# ADC.net
KiCad netlist of a schematic drawn in Altium Designer
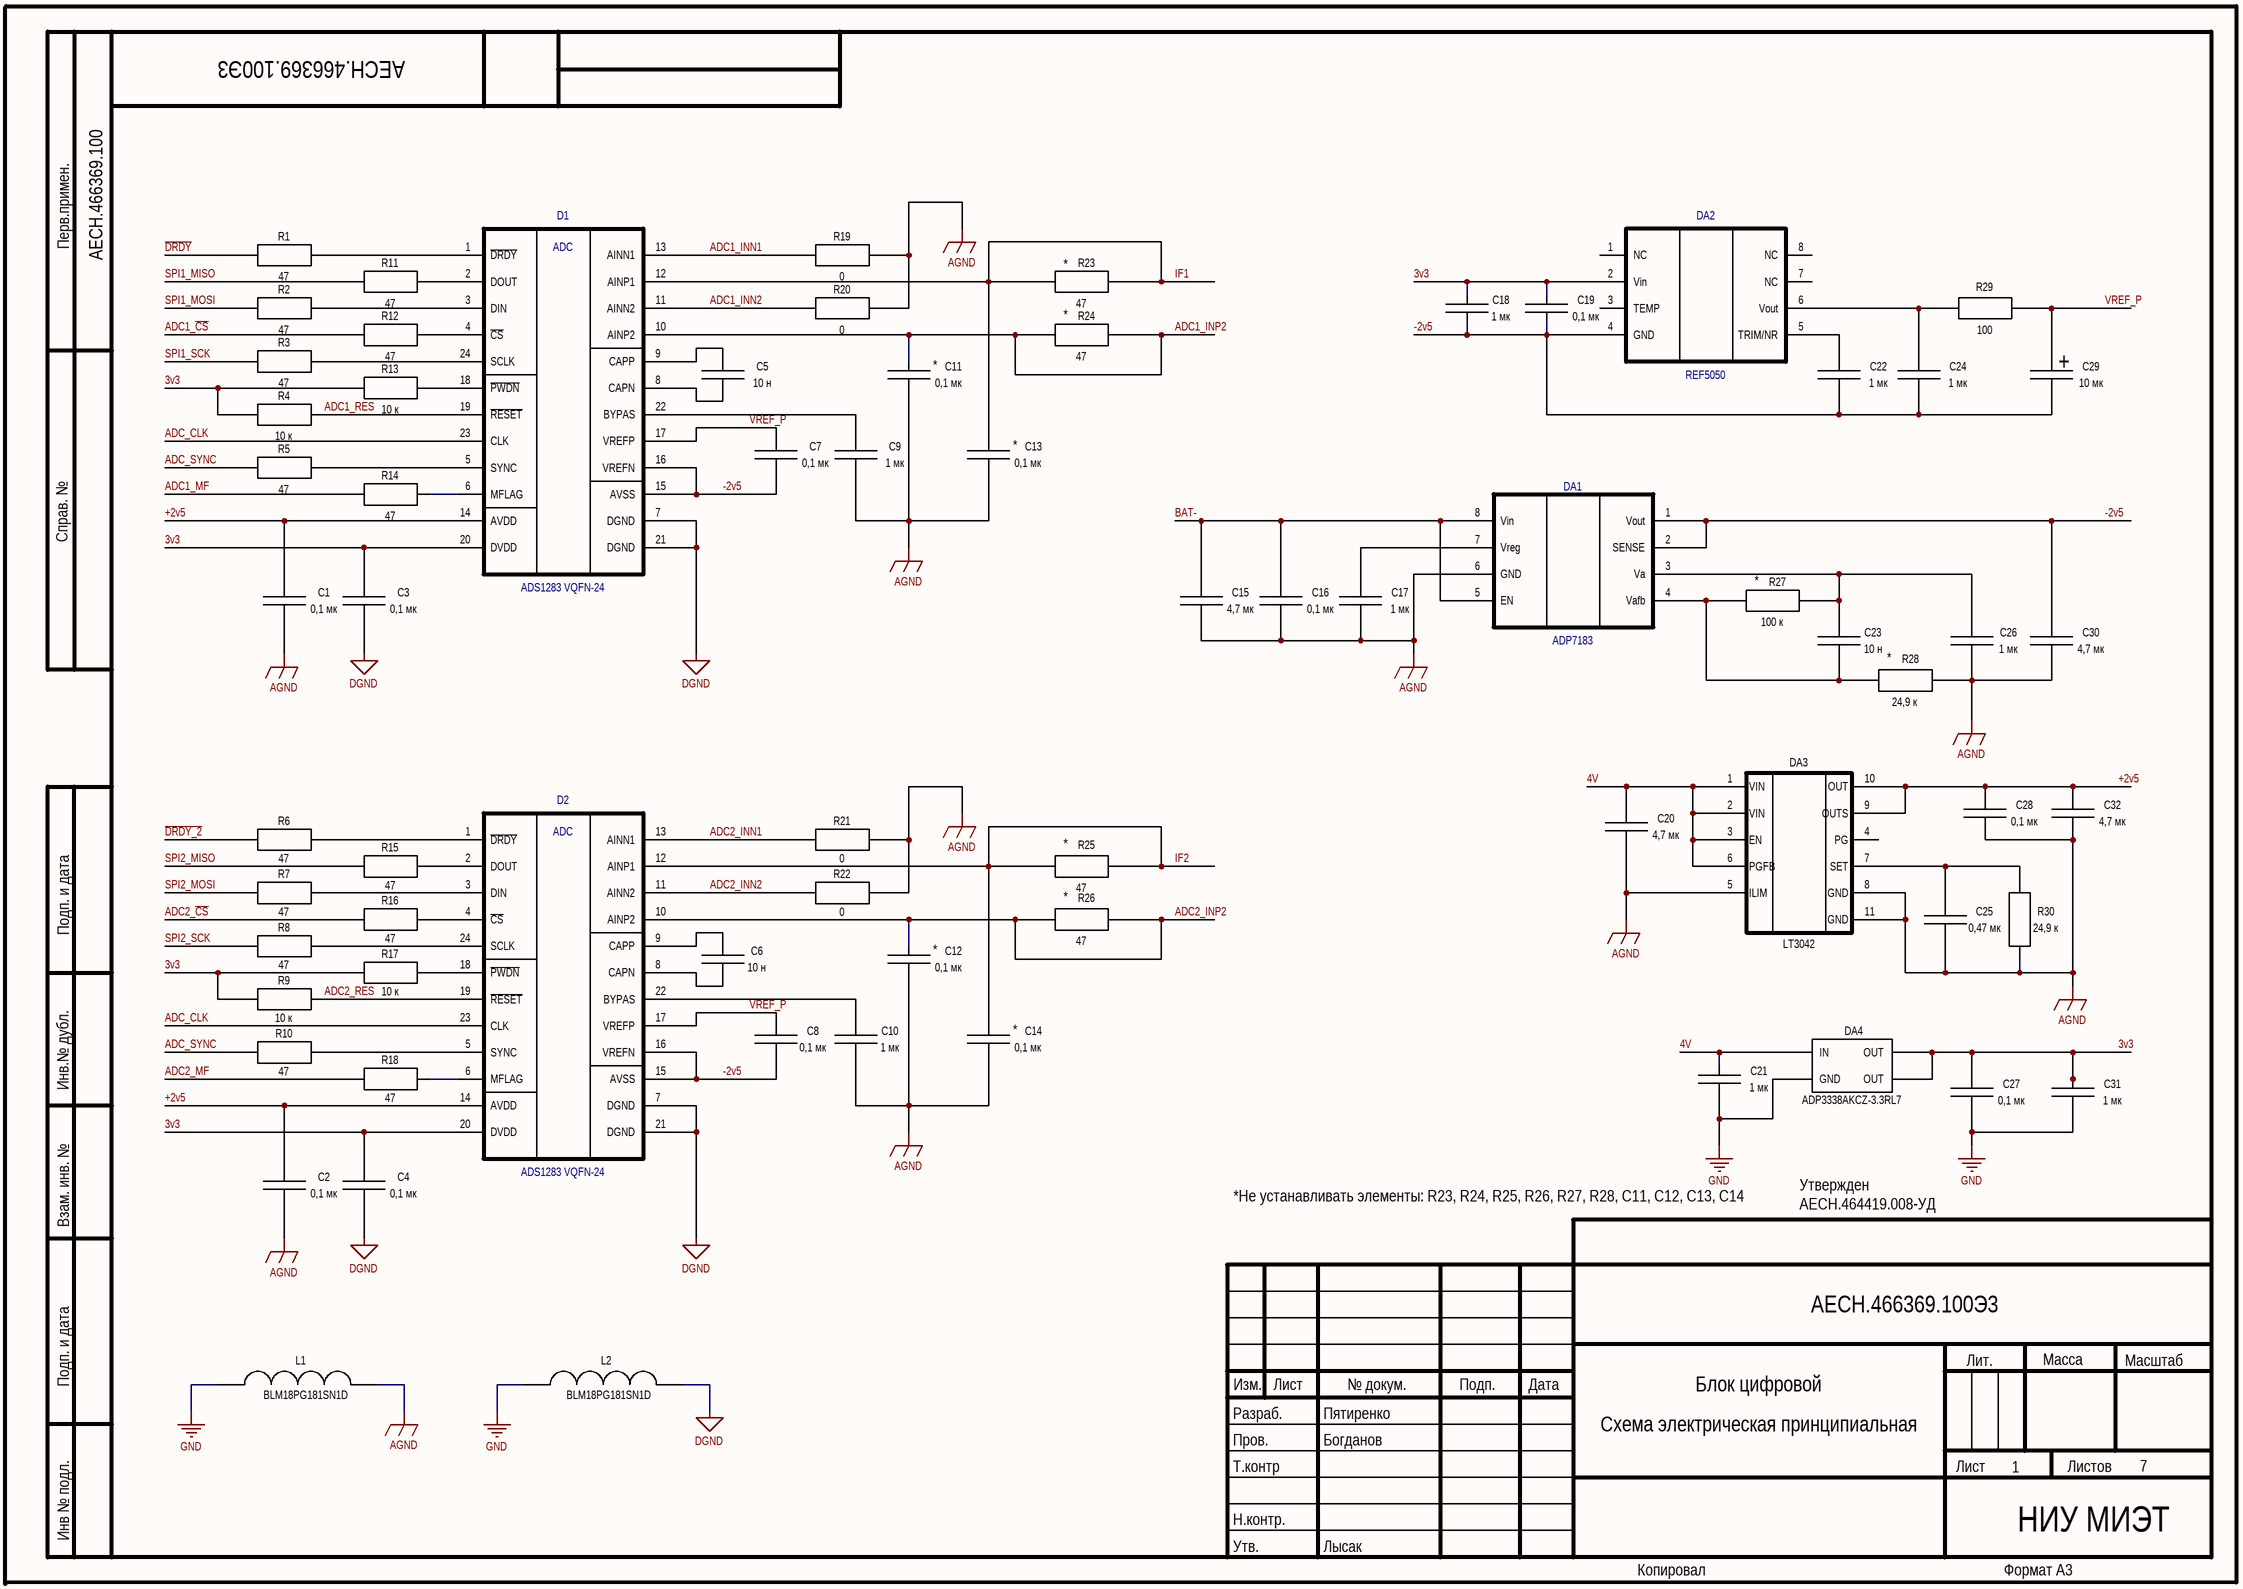
[diagram p0: ADC.SchDoc]

(export (version "E")
  (design (tool "Eeschema 10.0.6"))
  (components
    (comp (ref "C1")
      (value "0,1 мк")
      (footprint "C0603")
      (fields
        (field (name "TOLERANCE") "±10%")
        (field (name "VOLTAGE") "50 В")
        (field (name "PARTNUMBER") "GRM188R71H104KA93D")
      )
      (libsource (lib "5ko") (part "C"))
    )
    (comp (ref "C2")
      (value "0,1 мк")
      (footprint "C0603")
      (fields
        (field (name "TOLERANCE") "±10%")
        (field (name "VOLTAGE") "50 В")
        (field (name "PARTNUMBER") "GRM188R71H104KA93D")
      )
      (libsource (lib "5ko") (part "C"))
    )
    (comp (ref "C3")
      (value "0,1 мк")
      (footprint "C0603")
      (fields
        (field (name "TOLERANCE") "±10%")
        (field (name "VOLTAGE") "50 В")
        (field (name "PARTNUMBER") "GRM188R71H104KA93D")
      )
      (libsource (lib "5ko") (part "C"))
    )
    (comp (ref "C4")
      (value "0,1 мк")
      (footprint "C0603")
      (fields
        (field (name "TOLERANCE") "±10%")
        (field (name "VOLTAGE") "50 В")
        (field (name "PARTNUMBER") "GRM188R71H104KA93D")
      )
      (libsource (lib "5ko") (part "C"))
    )
    (comp (ref "C5")
      (value "10 н")
      (footprint "C0603")
      (fields
        (field (name "TOLERANCE") "±10%")
        (field (name "VOLTAGE") "100В")
        (field (name "PARTNUMBER") "GRM188R72A103KA01J")
      )
      (libsource (lib "5ko") (part "C"))
    )
    (comp (ref "C6")
      (value "10 н")
      (footprint "C0603")
      (fields
        (field (name "TOLERANCE") "±10%")
        (field (name "VOLTAGE") "100В")
        (field (name "PARTNUMBER") "GRM188R72A103KA01J")
      )
      (libsource (lib "5ko") (part "C"))
    )
    (comp (ref "C7")
      (value "0,1 мк")
      (footprint "C0603")
      (fields
        (field (name "TOLERANCE") "±10%")
        (field (name "VOLTAGE") "50 В")
        (field (name "PARTNUMBER") "GRM188R71H104KA93D")
      )
      (libsource (lib "5ko") (part "C"))
    )
    (comp (ref "C8")
      (value "0,1 мк")
      (footprint "C0603")
      (fields
        (field (name "TOLERANCE") "±10%")
        (field (name "VOLTAGE") "50 В")
        (field (name "PARTNUMBER") "GRM188R71H104KA93D")
      )
      (libsource (lib "5ko") (part "C"))
    )
    (comp (ref "C9")
      (value "1 мк")
      (footprint "C0603")
      (fields
        (field (name "TOLERANCE") "±10%")
        (field (name "VOLTAGE") "25 В")
        (field (name "PARTNUMBER") "GRM188R71E105KA12D")
      )
      (libsource (lib "5ko") (part "C"))
    )
    (comp (ref "C10")
      (value "1 мк")
      (footprint "C0603")
      (fields
        (field (name "TOLERANCE") "±10%")
        (field (name "VOLTAGE") "25 В")
        (field (name "PARTNUMBER") "GRM188R71E105KA12D")
      )
      (libsource (lib "5ko") (part "C"))
    )
    (comp (ref "C11")
      (value "0,1 мк")
      (footprint "C0603")
      (fields
        (field (name "TOLERANCE") "±10%")
        (field (name "VOLTAGE") "50 В")
        (field (name "PARTNUMBER") "GRM188R71H104KA93D")
      )
      (libsource (lib "5ko") (part "C"))
    )
    (comp (ref "C12")
      (value "0,1 мк")
      (footprint "C0603")
      (fields
        (field (name "TOLERANCE") "±10%")
        (field (name "VOLTAGE") "50 В")
        (field (name "PARTNUMBER") "GRM188R71H104KA93D")
      )
      (libsource (lib "5ko") (part "C"))
    )
    (comp (ref "C13")
      (value "0,1 мк")
      (footprint "C0603")
      (fields
        (field (name "TOLERANCE") "±10%")
        (field (name "VOLTAGE") "50 В")
        (field (name "PARTNUMBER") "GRM188R71H104KA93D")
      )
      (libsource (lib "5ko") (part "C"))
    )
    (comp (ref "C14")
      (value "0,1 мк")
      (footprint "C0603")
      (fields
        (field (name "TOLERANCE") "±10%")
        (field (name "VOLTAGE") "50 В")
        (field (name "PARTNUMBER") "GRM188R71H104KA93D")
      )
      (libsource (lib "5ko") (part "C"))
    )
    (comp (ref "C15")
      (value "4,7 мк")
      (footprint "C0603")
      (fields
        (field (name "TOLERANCE") "±10%")
        (field (name "VOLTAGE") "16 В")
        (field (name "PARTNUMBER") "GRM188Z71C475KE21D")
      )
      (libsource (lib "5ko") (part "C"))
    )
    (comp (ref "C16")
      (value "0,1 мк")
      (footprint "C0603")
      (fields
        (field (name "TOLERANCE") "±10%")
        (field (name "VOLTAGE") "50 В")
        (field (name "PARTNUMBER") "GRM188R71H104KA93D")
      )
      (libsource (lib "5ko") (part "C"))
    )
    (comp (ref "C17")
      (value "1 мк")
      (footprint "C0603")
      (fields
        (field (name "TOLERANCE") "±10%")
        (field (name "VOLTAGE") "25 В")
        (field (name "PARTNUMBER") "GRM188R71E105KA12D")
      )
      (libsource (lib "5ko") (part "C"))
    )
    (comp (ref "C18")
      (value "1 мк")
      (footprint "C0603")
      (fields
        (field (name "TOLERANCE") "±10%")
        (field (name "VOLTAGE") "25 В")
        (field (name "PARTNUMBER") "GRM188R71E105KA12D")
      )
      (libsource (lib "5ko") (part "C"))
    )
    (comp (ref "C19")
      (value "0,1 мк")
      (footprint "C0603")
      (fields
        (field (name "TOLERANCE") "±10%")
        (field (name "VOLTAGE") "50 В")
        (field (name "PARTNUMBER") "GRM188R71H104KA93D")
      )
      (libsource (lib "5ko") (part "C"))
    )
    (comp (ref "C20")
      (value "4,7 мк")
      (footprint "C0603")
      (fields
        (field (name "TOLERANCE") "±10%")
        (field (name "VOLTAGE") "16 В")
        (field (name "PARTNUMBER") "GRM188Z71C475KE21D")
      )
      (libsource (lib "5ko") (part "C"))
    )
    (comp (ref "C21")
      (value "1 мк")
      (footprint "C0603")
      (fields
        (field (name "TOLERANCE") "±10%")
        (field (name "VOLTAGE") "25 В")
        (field (name "PARTNUMBER") "GRM188R71E105KA12D")
      )
      (libsource (lib "5ko") (part "C"))
    )
    (comp (ref "C22")
      (value "1 мк")
      (footprint "C0603")
      (fields
        (field (name "TOLERANCE") "±10%")
        (field (name "VOLTAGE") "25 В")
        (field (name "PARTNUMBER") "GRM188R71E105KA12D")
      )
      (libsource (lib "5ko") (part "C"))
    )
    (comp (ref "C23")
      (value "10 н")
      (footprint "C0603")
      (fields
        (field (name "TOLERANCE") "±10%")
        (field (name "VOLTAGE") "100В")
        (field (name "PARTNUMBER") "GRM188R72A103KA01J")
      )
      (libsource (lib "5ko") (part "C"))
    )
    (comp (ref "C24")
      (value "1 мк")
      (footprint "C0603")
      (fields
        (field (name "TOLERANCE") "±10%")
        (field (name "VOLTAGE") "25 В")
        (field (name "PARTNUMBER") "GRM188R71E105KA12D")
      )
      (libsource (lib "5ko") (part "C"))
    )
    (comp (ref "C25")
      (value "0,47 мк")
      (footprint "C0603")
      (fields
        (field (name "TOLERANCE") "±10%")
        (field (name "VOLTAGE") "25 В")
        (field (name "PARTNUMBER") "GRM188R71E474KA12D")
      )
      (libsource (lib "5ko") (part "C"))
    )
    (comp (ref "C26")
      (value "1 мк")
      (footprint "C0603")
      (fields
        (field (name "TOLERANCE") "±10%")
        (field (name "VOLTAGE") "25 В")
        (field (name "PARTNUMBER") "GRM188R71E105KA12D")
      )
      (libsource (lib "5ko") (part "C"))
    )
    (comp (ref "C27")
      (value "0,1 мк")
      (footprint "C0603")
      (fields
        (field (name "TOLERANCE") "±10%")
        (field (name "VOLTAGE") "50 В")
        (field (name "PARTNUMBER") "GRM188R71H104KA93D")
      )
      (libsource (lib "5ko") (part "C"))
    )
    (comp (ref "C28")
      (value "0,1 мк")
      (footprint "C0603")
      (fields
        (field (name "TOLERANCE") "±10%")
        (field (name "VOLTAGE") "50 В")
        (field (name "PARTNUMBER") "GRM188R71H104KA93D")
      )
      (libsource (lib "5ko") (part "C"))
    )
    (comp (ref "C29")
      (value "10 мк")
      (footprint "Case A")
      (fields
        (field (name "TOLERANCE") "±10%")
        (field (name "VOLTAGE") "16 V")
        (field (name "PARTNUMBER") "TAJA106K016RNJ")
      )
      (libsource (lib "5ko") (part "C_el"))
    )
    (comp (ref "C30")
      (value "4,7 мк")
      (footprint "C0603")
      (fields
        (field (name "TOLERANCE") "±10%")
        (field (name "VOLTAGE") "16 В")
        (field (name "PARTNUMBER") "GRM188Z71C475KE21D")
      )
      (libsource (lib "5ko") (part "C"))
    )
    (comp (ref "C31")
      (value "1 мк")
      (footprint "C0603")
      (fields
        (field (name "TOLERANCE") "±10%")
        (field (name "VOLTAGE") "25 В")
        (field (name "PARTNUMBER") "GRM188R71E105KA12D")
      )
      (libsource (lib "5ko") (part "C"))
    )
    (comp (ref "C32")
      (value "4,7 мк")
      (footprint "C0603")
      (fields
        (field (name "TOLERANCE") "±10%")
        (field (name "VOLTAGE") "16 В")
        (field (name "PARTNUMBER") "GRM188Z71C475KE21D")
      )
      (libsource (lib "5ko") (part "C"))
    )
    (comp (ref "D1")
      (value "ADS1283 VQFN-24")
      (footprint "VQFN24_8x8x4x4")
      (description "ADC 2ch")
      (libsource (lib "5ko") (part "ADS1283"))
    )
    (comp (ref "D2")
      (value "ADS1283 VQFN-24")
      (footprint "VQFN24_8x8x4x4")
      (description "ADC 2ch")
      (libsource (lib "5ko") (part "ADS1283"))
    )
    (comp (ref "DA1") (value "ADP7183") (footprint "LFCSP-8") (libsource (lib "5ko") (part "ADP7183")))
    (comp (ref "DA2") (value "REF5050") (footprint "SOIC8") (libsource (lib "5ko") (part "REF50xx")))
    (comp (ref "DA3") (value "LT3042") (footprint "DFN-10 3x3") (libsource (lib "5ko") (part "LT3042")))
    (comp (ref "DA4")
      (value "ADP3338AKCZ-3.3RL7")
      (footprint "SOT-223")
      (libsource (lib "5ko") (part "LD1117S33"))
    )
    (comp (ref "L1") (value "BLM18PG181SN1D") (footprint "INDC_0603") (libsource (lib "5ko") (part "L_1")))
    (comp (ref "L2") (value "BLM18PG181SN1D") (footprint "INDC_0603") (libsource (lib "5ko") (part "L_1")))
    (comp (ref "R1")
      (value "47")
      (footprint "R0603")
      (fields
        (field (name "TOLERANCE") "±5%")
        (field (name "POWER") "0.1 Вт")
        (field (name "PARTNUMBER") "RC0603JR-0747RL")
      )
      (libsource (lib "5ko") (part "R"))
    )
    (comp (ref "R2")
      (value "47")
      (footprint "R0603")
      (fields
        (field (name "TOLERANCE") "±5%")
        (field (name "POWER") "0.1 Вт")
        (field (name "PARTNUMBER") "RC0603JR-0747RL")
      )
      (libsource (lib "5ko") (part "R"))
    )
    (comp (ref "R3")
      (value "47")
      (footprint "R0603")
      (fields
        (field (name "TOLERANCE") "±5%")
        (field (name "POWER") "0.1 Вт")
        (field (name "PARTNUMBER") "RC0603JR-0747RL")
      )
      (libsource (lib "5ko") (part "R"))
    )
    (comp (ref "R4")
      (value "10 к")
      (footprint "R0603")
      (fields
        (field (name "TOLERANCE") "±5%")
        (field (name "POWER") "0.1 Вт")
        (field (name "PARTNUMBER") "RC0603JR-0710KL")
      )
      (libsource (lib "5ko") (part "R"))
    )
    (comp (ref "R5")
      (value "47")
      (footprint "R0603")
      (fields
        (field (name "TOLERANCE") "±5%")
        (field (name "POWER") "0.1 Вт")
        (field (name "PARTNUMBER") "RC0603JR-0747RL")
      )
      (libsource (lib "5ko") (part "R"))
    )
    (comp (ref "R6")
      (value "47")
      (footprint "R0603")
      (fields
        (field (name "TOLERANCE") "±5%")
        (field (name "POWER") "0.1 Вт")
        (field (name "PARTNUMBER") "RC0603JR-0747RL")
      )
      (libsource (lib "5ko") (part "R"))
    )
    (comp (ref "R7")
      (value "47")
      (footprint "R0603")
      (fields
        (field (name "TOLERANCE") "±5%")
        (field (name "POWER") "0.1 Вт")
        (field (name "PARTNUMBER") "RC0603JR-0747RL")
      )
      (libsource (lib "5ko") (part "R"))
    )
    (comp (ref "R8")
      (value "47")
      (footprint "R0603")
      (fields
        (field (name "TOLERANCE") "±5%")
        (field (name "POWER") "0.1 Вт")
        (field (name "PARTNUMBER") "RC0603JR-0747RL")
      )
      (libsource (lib "5ko") (part "R"))
    )
    (comp (ref "R9")
      (value "10 к")
      (footprint "R0603")
      (fields
        (field (name "TOLERANCE") "±5%")
        (field (name "POWER") "0.1 Вт")
        (field (name "PARTNUMBER") "RC0603JR-0710KL")
      )
      (libsource (lib "5ko") (part "R"))
    )
    (comp (ref "R10")
      (value "47")
      (footprint "R0603")
      (fields
        (field (name "TOLERANCE") "±5%")
        (field (name "POWER") "0.1 Вт")
        (field (name "PARTNUMBER") "RC0603JR-0747RL")
      )
      (libsource (lib "5ko") (part "R"))
    )
    (comp (ref "R11")
      (value "47")
      (footprint "R0603")
      (fields
        (field (name "TOLERANCE") "±5%")
        (field (name "POWER") "0.1 Вт")
        (field (name "PARTNUMBER") "RC0603JR-0747RL")
      )
      (libsource (lib "5ko") (part "R"))
    )
    (comp (ref "R12")
      (value "47")
      (footprint "R0603")
      (fields
        (field (name "TOLERANCE") "±5%")
        (field (name "POWER") "0.1 Вт")
        (field (name "PARTNUMBER") "RC0603JR-0747RL")
      )
      (libsource (lib "5ko") (part "R"))
    )
    (comp (ref "R13")
      (value "10 к")
      (footprint "R0603")
      (fields
        (field (name "TOLERANCE") "±5%")
        (field (name "POWER") "0.1 Вт")
        (field (name "PARTNUMBER") "RC0603JR-0710KL")
      )
      (libsource (lib "5ko") (part "R"))
    )
    (comp (ref "R14")
      (value "47")
      (footprint "R0603")
      (fields
        (field (name "TOLERANCE") "±5%")
        (field (name "POWER") "0.1 Вт")
        (field (name "PARTNUMBER") "RC0603JR-0747RL")
      )
      (libsource (lib "5ko") (part "R"))
    )
    (comp (ref "R15")
      (value "47")
      (footprint "R0603")
      (fields
        (field (name "TOLERANCE") "±5%")
        (field (name "POWER") "0.1 Вт")
        (field (name "PARTNUMBER") "RC0603JR-0747RL")
      )
      (libsource (lib "5ko") (part "R"))
    )
    (comp (ref "R16")
      (value "47")
      (footprint "R0603")
      (fields
        (field (name "TOLERANCE") "±5%")
        (field (name "POWER") "0.1 Вт")
        (field (name "PARTNUMBER") "RC0603JR-0747RL")
      )
      (libsource (lib "5ko") (part "R"))
    )
    (comp (ref "R17")
      (value "10 к")
      (footprint "R0603")
      (fields
        (field (name "TOLERANCE") "±5%")
        (field (name "POWER") "0.1 Вт")
        (field (name "PARTNUMBER") "RC0603JR-0710KL")
      )
      (libsource (lib "5ko") (part "R"))
    )
    (comp (ref "R18")
      (value "47")
      (footprint "R0603")
      (fields
        (field (name "TOLERANCE") "±5%")
        (field (name "POWER") "0.1 Вт")
        (field (name "PARTNUMBER") "RC0603JR-0747RL")
      )
      (libsource (lib "5ko") (part "R"))
    )
    (comp (ref "R19")
      (value "0")
      (footprint "R0603")
      (fields
        (field (name "TOLERANCE") "±5%")
        (field (name "POWER") "0.1 Вт")
        (field (name "PARTNUMBER") "RC0603JR-070RL")
      )
      (libsource (lib "5ko") (part "R"))
    )
    (comp (ref "R20")
      (value "0")
      (footprint "R0603")
      (fields
        (field (name "TOLERANCE") "±5%")
        (field (name "POWER") "0.1 Вт")
        (field (name "PARTNUMBER") "RC0603JR-070RL")
      )
      (libsource (lib "5ko") (part "R"))
    )
    (comp (ref "R21")
      (value "0")
      (footprint "R0603")
      (fields
        (field (name "TOLERANCE") "±5%")
        (field (name "POWER") "0.1 Вт")
        (field (name "PARTNUMBER") "RC0603JR-070RL")
      )
      (libsource (lib "5ko") (part "R"))
    )
    (comp (ref "R22")
      (value "0")
      (footprint "R0603")
      (fields
        (field (name "TOLERANCE") "±5%")
        (field (name "POWER") "0.1 Вт")
        (field (name "PARTNUMBER") "RC0603JR-070RL")
      )
      (libsource (lib "5ko") (part "R"))
    )
    (comp (ref "R23")
      (value "47")
      (footprint "R0603")
      (fields
        (field (name "TOLERANCE") "±5%")
        (field (name "POWER") "0.1 Вт")
        (field (name "PARTNUMBER") "RC0603JR-0747RL")
      )
      (libsource (lib "5ko") (part "R"))
    )
    (comp (ref "R24")
      (value "47")
      (footprint "R0603")
      (fields
        (field (name "TOLERANCE") "±5%")
        (field (name "POWER") "0.1 Вт")
        (field (name "PARTNUMBER") "RC0603JR-0747RL")
      )
      (libsource (lib "5ko") (part "R"))
    )
    (comp (ref "R25")
      (value "47")
      (footprint "R0603")
      (fields
        (field (name "TOLERANCE") "±5%")
        (field (name "POWER") "0.1 Вт")
        (field (name "PARTNUMBER") "RC0603JR-0747RL")
      )
      (libsource (lib "5ko") (part "R"))
    )
    (comp (ref "R26")
      (value "47")
      (footprint "R0603")
      (fields
        (field (name "TOLERANCE") "±5%")
        (field (name "POWER") "0.1 Вт")
        (field (name "PARTNUMBER") "RC0603JR-0747RL")
      )
      (libsource (lib "5ko") (part "R"))
    )
    (comp (ref "R27")
      (value "100 к")
      (footprint "R0603")
      (fields
        (field (name "TOLERANCE") "±1%")
        (field (name "POWER") "0.1 Вт")
        (field (name "PARTNUMBER") "RC0603FR-07100KL")
      )
      (libsource (lib "5ko") (part "R"))
    )
    (comp (ref "R28")
      (value "24,9 к")
      (footprint "R0603")
      (fields
        (field (name "TOLERANCE") "±1%")
        (field (name "POWER") "0.1 Вт")
        (field (name "PARTNUMBER") "RC0603FR-0724K9L")
      )
      (libsource (lib "5ko") (part "R"))
    )
    (comp (ref "R29")
      (value "100")
      (footprint "R0603")
      (fields
        (field (name "TOLERANCE") "±5%")
        (field (name "POWER") "0.1 Вт")
        (field (name "PARTNUMBER") "RC0603JR-07100RL")
      )
      (libsource (lib "5ko") (part "R"))
    )
    (comp (ref "R30")
      (value "24,9 к")
      (footprint "R0603")
      (fields
        (field (name "TOLERANCE") "±1%")
        (field (name "POWER") "0.1 Вт")
        (field (name "PARTNUMBER") "RC0603FR-0724K9L")
      )
      (libsource (lib "5ko") (part "R"))
    )
  )
  (nets
    (net (code "1") (name "/+2v5") (class "Default")
      (node (ref "C1") (pin "1") (pinfunction "1_1") (pintype "passive"))
      (node (ref "C2") (pin "1") (pinfunction "1_1") (pintype "passive"))
      (node (ref "C28") (pin "1") (pinfunction "1_1") (pintype "passive"))
      (node (ref "C32") (pin "1") (pinfunction "1_1") (pintype "passive"))
      (node (ref "D1") (pin "14") (pinfunction "AVDD_14") (pintype "passive"))
      (node (ref "D2") (pin "14") (pinfunction "AVDD_14") (pintype "passive"))
      (node (ref "DA3") (pin "10") (pinfunction "OUT_10") (pintype "passive"))
      (node (ref "DA3") (pin "9") (pinfunction "OUTS_9") (pintype "passive"))
    )
    (net (code "2") (name "/-2v5") (class "Default")
      (node (ref "C18") (pin "2") (pinfunction "2_2") (pintype "passive"))
      (node (ref "C19") (pin "2") (pinfunction "2_2") (pintype "passive"))
      (node (ref "C22") (pin "2") (pinfunction "2_2") (pintype "passive"))
      (node (ref "C24") (pin "2") (pinfunction "2_2") (pintype "passive"))
      (node (ref "C29") (pin "2") (pinfunction "2_2") (pintype "passive"))
      (node (ref "C30") (pin "1") (pinfunction "1_1") (pintype "passive"))
      (node (ref "C7") (pin "2") (pinfunction "2_2") (pintype "passive"))
      (node (ref "C8") (pin "2") (pinfunction "2_2") (pintype "passive"))
      (node (ref "D1") (pin "15") (pinfunction "AVSS_15") (pintype "passive"))
      (node (ref "D1") (pin "16") (pinfunction "VREFN_16") (pintype "passive"))
      (node (ref "D2") (pin "15") (pinfunction "AVSS_15") (pintype "passive"))
      (node (ref "D2") (pin "16") (pinfunction "VREFN_16") (pintype "passive"))
      (node (ref "DA1") (pin "1") (pinfunction "Vout_1") (pintype "passive"))
      (node (ref "DA1") (pin "2") (pinfunction "SENSE_2") (pintype "passive"))
      (node (ref "DA2") (pin "4") (pinfunction "GND_4") (pintype "passive"))
    )
    (net (code "3") (name "/3v3") (class "Default")
      (node (ref "C18") (pin "1") (pinfunction "1_1") (pintype "passive"))
      (node (ref "C19") (pin "1") (pinfunction "1_1") (pintype "passive"))
      (node (ref "C27") (pin "1") (pinfunction "1_1") (pintype "passive"))
      (node (ref "C3") (pin "1") (pinfunction "1_1") (pintype "passive"))
      (node (ref "C31") (pin "1") (pinfunction "1_1") (pintype "passive"))
      (node (ref "C4") (pin "1") (pinfunction "1_1") (pintype "passive"))
      (node (ref "D1") (pin "20") (pinfunction "DVDD_20") (pintype "passive"))
      (node (ref "D2") (pin "20") (pinfunction "DVDD_20") (pintype "passive"))
      (node (ref "DA2") (pin "2") (pinfunction "Vin_2") (pintype "passive"))
      (node (ref "DA4") (pin "2") (pinfunction "OUT_2") (pintype "passive"))
      (node (ref "DA4") (pin "4") (pinfunction "OUT_4") (pintype "passive"))
      (node (ref "R13") (pin "1") (pinfunction "1_1") (pintype "passive"))
      (node (ref "R17") (pin "1") (pinfunction "1_1") (pintype "passive"))
      (node (ref "R4") (pin "1") (pinfunction "1_1") (pintype "passive"))
      (node (ref "R9") (pin "1") (pinfunction "1_1") (pintype "passive"))
    )
    (net (code "4") (name "/4V") (class "Default")
      (node (ref "C20") (pin "1") (pinfunction "1_1") (pintype "passive"))
      (node (ref "C21") (pin "1") (pinfunction "1_1") (pintype "passive"))
      (node (ref "DA3") (pin "1") (pinfunction "VIN_1") (pintype "passive"))
      (node (ref "DA3") (pin "2") (pinfunction "VIN_2") (pintype "passive"))
      (node (ref "DA3") (pin "3") (pinfunction "EN_3") (pintype "passive"))
      (node (ref "DA3") (pin "6") (pinfunction "PGFB_6") (pintype "passive"))
      (node (ref "DA4") (pin "3") (pinfunction "IN_3") (pintype "passive"))
    )
    (net (code "5") (name "/ADC1_INN1") (class "Default")
      (node (ref "D1") (pin "13") (pinfunction "AINN1_13") (pintype "passive"))
      (node (ref "R19") (pin "1") (pinfunction "1_1") (pintype "passive"))
    )
    (net (code "6") (name "/ADC1_INN2") (class "Default")
      (node (ref "D1") (pin "11") (pinfunction "AINN2_11") (pintype "passive"))
      (node (ref "R20") (pin "1") (pinfunction "1_1") (pintype "passive"))
    )
    (net (code "7") (name "/ADC1_INP2") (class "Default")
      (node (ref "C11") (pin "1") (pinfunction "1_1") (pintype "passive"))
      (node (ref "D1") (pin "10") (pinfunction "AINP2_10") (pintype "passive"))
      (node (ref "R24") (pin "1") (pinfunction "1_1") (pintype "passive"))
      (node (ref "R24") (pin "2") (pinfunction "2_2") (pintype "passive"))
    )
    (net (code "8") (name "/ADC1_MF") (class "Default")
      (node (ref "R14") (pin "1") (pinfunction "1_1") (pintype "passive"))
    )
    (net (code "9") (name "/ADC1_RES") (class "Default")
      (node (ref "D1") (pin "19") (pinfunction "~{RESET}_19") (pintype "passive"))
      (node (ref "R4") (pin "2") (pinfunction "2_2") (pintype "passive"))
    )
    (net (code "10") (name "/ADC1_~{CS}") (class "Default")
      (node (ref "R12") (pin "1") (pinfunction "1_1") (pintype "passive"))
    )
    (net (code "11") (name "/ADC2_INN1") (class "Default")
      (node (ref "D2") (pin "13") (pinfunction "AINN1_13") (pintype "passive"))
      (node (ref "R21") (pin "1") (pinfunction "1_1") (pintype "passive"))
    )
    (net (code "12") (name "/ADC2_INN2") (class "Default")
      (node (ref "D2") (pin "11") (pinfunction "AINN2_11") (pintype "passive"))
      (node (ref "R22") (pin "1") (pinfunction "1_1") (pintype "passive"))
    )
    (net (code "13") (name "/ADC2_INP2") (class "Default")
      (node (ref "C12") (pin "1") (pinfunction "1_1") (pintype "passive"))
      (node (ref "D2") (pin "10") (pinfunction "AINP2_10") (pintype "passive"))
      (node (ref "R26") (pin "1") (pinfunction "1_1") (pintype "passive"))
      (node (ref "R26") (pin "2") (pinfunction "2_2") (pintype "passive"))
    )
    (net (code "14") (name "/ADC2_MF") (class "Default")
      (node (ref "R18") (pin "1") (pinfunction "1_1") (pintype "passive"))
    )
    (net (code "15") (name "/ADC2_RES") (class "Default")
      (node (ref "D2") (pin "19") (pinfunction "~{RESET}_19") (pintype "passive"))
      (node (ref "R9") (pin "2") (pinfunction "2_2") (pintype "passive"))
    )
    (net (code "16") (name "/ADC2_~{CS}") (class "Default")
      (node (ref "R16") (pin "1") (pinfunction "1_1") (pintype "passive"))
    )
    (net (code "17") (name "/ADC_CLK") (class "Default")
      (node (ref "D1") (pin "23") (pinfunction "CLK_23") (pintype "passive"))
      (node (ref "D2") (pin "23") (pinfunction "CLK_23") (pintype "passive"))
    )
    (net (code "18") (name "/ADC_SYNC") (class "Default")
      (node (ref "R10") (pin "1") (pinfunction "1_1") (pintype "passive"))
      (node (ref "R5") (pin "1") (pinfunction "1_1") (pintype "passive"))
    )
    (net (code "19") (name "/BAT-") (class "Default")
      (node (ref "C15") (pin "1") (pinfunction "1_1") (pintype "passive"))
      (node (ref "C16") (pin "1") (pinfunction "1_1") (pintype "passive"))
      (node (ref "DA1") (pin "5") (pinfunction "EN_5") (pintype "passive"))
      (node (ref "DA1") (pin "8") (pinfunction "Vin_8") (pintype "passive"))
    )
    (net (code "20") (name "/IF1") (class "Default")
      (node (ref "C13") (pin "1") (pinfunction "1_1") (pintype "passive"))
      (node (ref "D1") (pin "12") (pinfunction "AINP1_12") (pintype "passive"))
      (node (ref "R23") (pin "1") (pinfunction "1_1") (pintype "passive"))
      (node (ref "R23") (pin "2") (pinfunction "2_2") (pintype "passive"))
    )
    (net (code "21") (name "/IF2") (class "Default")
      (node (ref "C14") (pin "1") (pinfunction "1_1") (pintype "passive"))
      (node (ref "D2") (pin "12") (pinfunction "AINP1_12") (pintype "passive"))
      (node (ref "R25") (pin "1") (pinfunction "1_1") (pintype "passive"))
      (node (ref "R25") (pin "2") (pinfunction "2_2") (pintype "passive"))
    )
    (net (code "22") (name "/SPI1_MISO") (class "Default")
      (node (ref "R11") (pin "1") (pinfunction "1_1") (pintype "passive"))
    )
    (net (code "23") (name "/SPI1_MOSI") (class "Default")
      (node (ref "R2") (pin "1") (pinfunction "1_1") (pintype "passive"))
    )
    (net (code "24") (name "/SPI1_SCK") (class "Default")
      (node (ref "R3") (pin "1") (pinfunction "1_1") (pintype "passive"))
    )
    (net (code "25") (name "/SPI2_MISO") (class "Default")
      (node (ref "R15") (pin "1") (pinfunction "1_1") (pintype "passive"))
    )
    (net (code "26") (name "/SPI2_MOSI") (class "Default")
      (node (ref "R7") (pin "1") (pinfunction "1_1") (pintype "passive"))
    )
    (net (code "27") (name "/SPI2_SCK") (class "Default")
      (node (ref "R8") (pin "1") (pinfunction "1_1") (pintype "passive"))
    )
    (net (code "28") (name "/VREF_P") (class "Default")
      (node (ref "C29") (pin "1") (pinfunction "1_1") (pintype "passive"))
      (node (ref "C7") (pin "1") (pinfunction "1_1") (pintype "passive"))
      (node (ref "C8") (pin "1") (pinfunction "1_1") (pintype "passive"))
      (node (ref "D1") (pin "17") (pinfunction "VREFP_17") (pintype "passive"))
      (node (ref "D2") (pin "17") (pinfunction "VREFP_17") (pintype "passive"))
      (node (ref "R29") (pin "2") (pinfunction "2_2") (pintype "passive"))
    )
    (net (code "29") (name "/~{DRDY_2}") (class "Default")
      (node (ref "R6") (pin "1") (pinfunction "1_1") (pintype "passive"))
    )
    (net (code "30") (name "/~{DRDY}") (class "Default")
      (node (ref "R1") (pin "1") (pinfunction "1_1") (pintype "passive"))
    )
    (net (code "31") (name "AGND") (class "Default")
      (node (ref "C1") (pin "2") (pinfunction "2_2") (pintype "passive"))
      (node (ref "C10") (pin "2") (pinfunction "2_2") (pintype "passive"))
      (node (ref "C11") (pin "2") (pinfunction "2_2") (pintype "passive"))
      (node (ref "C12") (pin "2") (pinfunction "2_2") (pintype "passive"))
      (node (ref "C13") (pin "2") (pinfunction "2_2") (pintype "passive"))
      (node (ref "C14") (pin "2") (pinfunction "2_2") (pintype "passive"))
      (node (ref "C15") (pin "2") (pinfunction "2_2") (pintype "passive"))
      (node (ref "C16") (pin "2") (pinfunction "2_2") (pintype "passive"))
      (node (ref "C17") (pin "2") (pinfunction "2_2") (pintype "passive"))
      (node (ref "C2") (pin "2") (pinfunction "2_2") (pintype "passive"))
      (node (ref "C20") (pin "2") (pinfunction "2_2") (pintype "passive"))
      (node (ref "C25") (pin "2") (pinfunction "2_2") (pintype "passive"))
      (node (ref "C26") (pin "2") (pinfunction "2_2") (pintype "passive"))
      (node (ref "C28") (pin "2") (pinfunction "2_2") (pintype "passive"))
      (node (ref "C30") (pin "2") (pinfunction "2_2") (pintype "passive"))
      (node (ref "C32") (pin "2") (pinfunction "2_2") (pintype "passive"))
      (node (ref "C9") (pin "2") (pinfunction "2_2") (pintype "passive"))
      (node (ref "DA1") (pin "6") (pinfunction "GND_6") (pintype "passive"))
      (node (ref "DA3") (pin "11") (pinfunction "GND_11") (pintype "passive"))
      (node (ref "DA3") (pin "5") (pinfunction "ILIM_5") (pintype "passive"))
      (node (ref "DA3") (pin "8") (pinfunction "GND_8") (pintype "passive"))
      (node (ref "L1") (pin "1") (pinfunction "1_1") (pintype "passive"))
      (node (ref "R19") (pin "2") (pinfunction "2_2") (pintype "passive"))
      (node (ref "R20") (pin "2") (pinfunction "2_2") (pintype "passive"))
      (node (ref "R21") (pin "2") (pinfunction "2_2") (pintype "passive"))
      (node (ref "R22") (pin "2") (pinfunction "2_2") (pintype "passive"))
      (node (ref "R28") (pin "2") (pinfunction "2_2") (pintype "passive"))
      (node (ref "R30") (pin "1") (pinfunction "1_1") (pintype "passive"))
    )
    (net (code "32") (name "DGND") (class "Default")
      (node (ref "C3") (pin "2") (pinfunction "2_2") (pintype "passive"))
      (node (ref "C4") (pin "2") (pinfunction "2_2") (pintype "passive"))
      (node (ref "D1") (pin "21") (pinfunction "DGND_21") (pintype "passive"))
      (node (ref "D1") (pin "7") (pinfunction "DGND_7") (pintype "passive"))
      (node (ref "D2") (pin "21") (pinfunction "DGND_21") (pintype "passive"))
      (node (ref "D2") (pin "7") (pinfunction "DGND_7") (pintype "passive"))
      (node (ref "L2") (pin "1") (pinfunction "1_1") (pintype "passive"))
    )
    (net (code "33") (name "GND") (class "Default")
      (node (ref "C21") (pin "2") (pinfunction "2_2") (pintype "passive"))
      (node (ref "C27") (pin "2") (pinfunction "2_2") (pintype "passive"))
      (node (ref "C31") (pin "2") (pinfunction "2_2") (pintype "passive"))
      (node (ref "DA4") (pin "1") (pinfunction "GND_1") (pintype "passive"))
      (node (ref "L1") (pin "2") (pinfunction "2_2") (pintype "passive"))
      (node (ref "L2") (pin "2") (pinfunction "2_2") (pintype "passive"))
    )
    (net (code "34") (name "Net-(D1-BYPAS)") (class "Default")
      (node (ref "C9") (pin "1") (pinfunction "1_1") (pintype "passive"))
      (node (ref "D1") (pin "22") (pinfunction "BYPAS_22") (pintype "passive"))
    )
    (net (code "35") (name "Net-(D1-CAPN)") (class "Default")
      (node (ref "C5") (pin "1") (pinfunction "1_1") (pintype "passive"))
      (node (ref "D1") (pin "8") (pinfunction "CAPN_8") (pintype "passive"))
    )
    (net (code "36") (name "Net-(D1-CAPP)") (class "Default")
      (node (ref "C5") (pin "2") (pinfunction "2_2") (pintype "passive"))
      (node (ref "D1") (pin "9") (pinfunction "CAPP_9") (pintype "passive"))
    )
    (net (code "37") (name "Net-(D1-DIN)") (class "Default")
      (node (ref "D1") (pin "3") (pinfunction "DIN_3") (pintype "passive"))
      (node (ref "R2") (pin "2") (pinfunction "2_2") (pintype "passive"))
    )
    (net (code "38") (name "Net-(D1-DOUT)") (class "Default")
      (node (ref "D1") (pin "2") (pinfunction "DOUT_2") (pintype "passive"))
      (node (ref "R11") (pin "2") (pinfunction "2_2") (pintype "passive"))
    )
    (net (code "39") (name "Net-(D1-MFLAG)") (class "Default")
      (node (ref "D1") (pin "6") (pinfunction "MFLAG_6") (pintype "passive"))
      (node (ref "R14") (pin "2") (pinfunction "2_2") (pintype "passive"))
    )
    (net (code "40") (name "Net-(D1-SCLK)") (class "Default")
      (node (ref "D1") (pin "24") (pinfunction "SCLK_24") (pintype "passive"))
      (node (ref "R3") (pin "2") (pinfunction "2_2") (pintype "passive"))
    )
    (net (code "41") (name "Net-(D1-SYNC)") (class "Default")
      (node (ref "D1") (pin "5") (pinfunction "SYNC_5") (pintype "passive"))
      (node (ref "R5") (pin "2") (pinfunction "2_2") (pintype "passive"))
    )
    (net (code "42") (name "Net-(D1-~{CS})") (class "Default")
      (node (ref "D1") (pin "4") (pinfunction "~{CS}_4") (pintype "passive"))
      (node (ref "R12") (pin "2") (pinfunction "2_2") (pintype "passive"))
    )
    (net (code "43") (name "Net-(D1-~{DRDY})") (class "Default")
      (node (ref "D1") (pin "1") (pinfunction "~{DRDY}_1") (pintype "passive"))
      (node (ref "R1") (pin "2") (pinfunction "2_2") (pintype "passive"))
    )
    (net (code "44") (name "Net-(D1-~{PWDN})") (class "Default")
      (node (ref "D1") (pin "18") (pinfunction "~{PWDN}_18") (pintype "passive"))
      (node (ref "R13") (pin "2") (pinfunction "2_2") (pintype "passive"))
    )
    (net (code "45") (name "Net-(D2-BYPAS)") (class "Default")
      (node (ref "C10") (pin "1") (pinfunction "1_1") (pintype "passive"))
      (node (ref "D2") (pin "22") (pinfunction "BYPAS_22") (pintype "passive"))
    )
    (net (code "46") (name "Net-(D2-CAPN)") (class "Default")
      (node (ref "C6") (pin "1") (pinfunction "1_1") (pintype "passive"))
      (node (ref "D2") (pin "8") (pinfunction "CAPN_8") (pintype "passive"))
    )
    (net (code "47") (name "Net-(D2-CAPP)") (class "Default")
      (node (ref "C6") (pin "2") (pinfunction "2_2") (pintype "passive"))
      (node (ref "D2") (pin "9") (pinfunction "CAPP_9") (pintype "passive"))
    )
    (net (code "48") (name "Net-(D2-DIN)") (class "Default")
      (node (ref "D2") (pin "3") (pinfunction "DIN_3") (pintype "passive"))
      (node (ref "R7") (pin "2") (pinfunction "2_2") (pintype "passive"))
    )
    (net (code "49") (name "Net-(D2-DOUT)") (class "Default")
      (node (ref "D2") (pin "2") (pinfunction "DOUT_2") (pintype "passive"))
      (node (ref "R15") (pin "2") (pinfunction "2_2") (pintype "passive"))
    )
    (net (code "50") (name "Net-(D2-MFLAG)") (class "Default")
      (node (ref "D2") (pin "6") (pinfunction "MFLAG_6") (pintype "passive"))
      (node (ref "R18") (pin "2") (pinfunction "2_2") (pintype "passive"))
    )
    (net (code "51") (name "Net-(D2-SCLK)") (class "Default")
      (node (ref "D2") (pin "24") (pinfunction "SCLK_24") (pintype "passive"))
      (node (ref "R8") (pin "2") (pinfunction "2_2") (pintype "passive"))
    )
    (net (code "52") (name "Net-(D2-SYNC)") (class "Default")
      (node (ref "D2") (pin "5") (pinfunction "SYNC_5") (pintype "passive"))
      (node (ref "R10") (pin "2") (pinfunction "2_2") (pintype "passive"))
    )
    (net (code "53") (name "Net-(D2-~{CS})") (class "Default")
      (node (ref "D2") (pin "4") (pinfunction "~{CS}_4") (pintype "passive"))
      (node (ref "R16") (pin "2") (pinfunction "2_2") (pintype "passive"))
    )
    (net (code "54") (name "Net-(D2-~{DRDY})") (class "Default")
      (node (ref "D2") (pin "1") (pinfunction "~{DRDY}_1") (pintype "passive"))
      (node (ref "R6") (pin "2") (pinfunction "2_2") (pintype "passive"))
    )
    (net (code "55") (name "Net-(D2-~{PWDN})") (class "Default")
      (node (ref "D2") (pin "18") (pinfunction "~{PWDN}_18") (pintype "passive"))
      (node (ref "R17") (pin "2") (pinfunction "2_2") (pintype "passive"))
    )
    (net (code "56") (name "Net-(DA1-Va)") (class "Default")
      (node (ref "C23") (pin "2") (pinfunction "2_2") (pintype "passive"))
      (node (ref "C26") (pin "1") (pinfunction "1_1") (pintype "passive"))
      (node (ref "DA1") (pin "3") (pinfunction "Va_3") (pintype "passive"))
      (node (ref "R27") (pin "2") (pinfunction "2_2") (pintype "passive"))
    )
    (net (code "57") (name "Net-(DA1-Vafb)") (class "Default")
      (node (ref "C23") (pin "1") (pinfunction "1_1") (pintype "passive"))
      (node (ref "DA1") (pin "4") (pinfunction "Vafb_4") (pintype "passive"))
      (node (ref "R27") (pin "1") (pinfunction "1_1") (pintype "passive"))
      (node (ref "R28") (pin "1") (pinfunction "1_1") (pintype "passive"))
    )
    (net (code "58") (name "Net-(DA1-Vreg)") (class "Default")
      (node (ref "C17") (pin "1") (pinfunction "1_1") (pintype "passive"))
      (node (ref "DA1") (pin "7") (pinfunction "Vreg_7") (pintype "passive"))
    )
    (net (code "59") (name "Net-(DA2-TRIM{slash}NR)") (class "Default")
      (node (ref "C22") (pin "1") (pinfunction "1_1") (pintype "passive"))
      (node (ref "DA2") (pin "5") (pinfunction "TRIM/NR_5") (pintype "passive"))
    )
    (net (code "60") (name "Net-(DA2-Vout)") (class "Default")
      (node (ref "C24") (pin "1") (pinfunction "1_1") (pintype "passive"))
      (node (ref "DA2") (pin "6") (pinfunction "Vout_6") (pintype "passive"))
      (node (ref "R29") (pin "1") (pinfunction "1_1") (pintype "passive"))
    )
    (net (code "61") (name "Net-(DA3-SET)") (class "Default")
      (node (ref "C25") (pin "1") (pinfunction "1_1") (pintype "passive"))
      (node (ref "DA3") (pin "7") (pinfunction "SET_7") (pintype "passive"))
      (node (ref "R30") (pin "2") (pinfunction "2_2") (pintype "passive"))
    )
    (net (code "62") (name "unconnected-(DA2-NC-Pad1)") (class "Default")
      (node (ref "DA2") (pin "1") (pinfunction "NC_1") (pintype "passive"))
    )
    (net (code "63") (name "unconnected-(DA2-NC-Pad7)") (class "Default")
      (node (ref "DA2") (pin "7") (pinfunction "NC_7") (pintype "passive"))
    )
    (net (code "64") (name "unconnected-(DA2-NC-Pad8)") (class "Default")
      (node (ref "DA2") (pin "8") (pinfunction "NC_8") (pintype "passive"))
    )
    (net (code "65") (name "unconnected-(DA2-TEMP-Pad3)") (class "Default")
      (node (ref "DA2") (pin "3") (pinfunction "TEMP_3") (pintype "passive"))
    )
    (net (code "66") (name "unconnected-(DA3-PG-Pad4)") (class "Default")
      (node (ref "DA3") (pin "4") (pinfunction "PG_4") (pintype "passive"))
    )
  )
)
